# BATTERY-PCM.net
KiCad netlist of a schematic drawn in Altium Designer
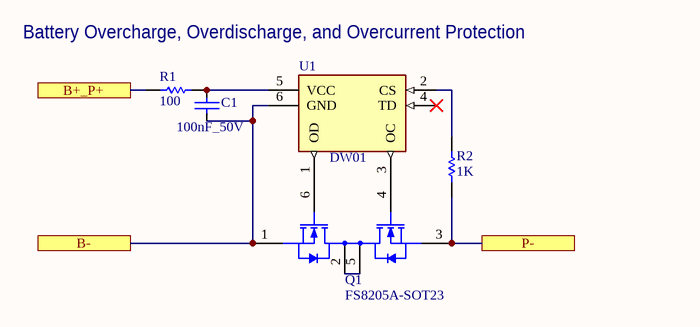
[diagram p0: BATTERY-PCM.SchDoc]

(export (version "E")
  (design (tool "Eeschema 10.0.6"))
  (components
    (comp (ref "C1")
      (value "100nF_50V")
      (footprint "C0402")
      (description "C0805 0.10 μF X7R 30ppm/°C 10.00% 50 V")
      (fields
        (field (name "MANUFACTURER") "KEMET")
        (field (name "MANUFACTURER PART NUMBER") "C0805C104K5RAC7411")
      )
      (libsource (lib "CustomLib-Package") (part "CAPACITOR"))
    )
    (comp (ref "Q1")
      (value "FS8205A-SOT23")
      (footprint "SOT-23-6")
      (description "Dual N-Channel Enhancement Mode Power MOSFET")
      (fields (field (name "MF") "Fortune Semiconductor") (field (name "MP") "FS8205A"))
      (libsource (lib "CustomLib-Package") (part "FS8205A-SOT23"))
    )
    (comp (ref "R1")
      (value "100")
      (footprint "R0402")
      (description "RES SMD 10K OHM 1% 1/8W 0805")
      (fields (field (name "TOLERANCE") "1%") (field (name "Comment") "CRG0805F10K"))
      (libsource (lib "CustomLib-Package") (part "RESISTOR"))
    )
    (comp (ref "R2")
      (value "1K")
      (footprint "R0402")
      (description "RES SMD 10K OHM 1% 1/8W 0805")
      (fields (field (name "TOLERANCE") "1%") (field (name "Comment") "CRG0805F10K"))
      (libsource (lib "CustomLib-Package") (part "RESISTOR"))
    )
    (comp (ref "U1")
      (value "DW01")
      (footprint "SOT-23-6")
      (description "One Cell Lithium-ion/Polymer Battery Protection IC")
      (fields (field (name "MF") "Fortune Semiconductor") (field (name "MP") "DW01A"))
      (libsource (lib "CustomLib-Package") (part "DW01"))
    )
  )
  (nets
    (net (code "1") (name "/B+_P+") (class "Default")
      (node (ref "R1") (pin "1") (pinfunction "1_1") (pintype "passive"))
    )
    (net (code "2") (name "/B-") (class "Default")
      (node (ref "C1") (pin "2") (pinfunction "2_2") (pintype "passive"))
      (node (ref "Q1") (pin "1") (pinfunction "S1_1") (pintype "passive"))
      (node (ref "U1") (pin "6") (pinfunction "GND_6") (pintype "power_in"))
    )
    (net (code "3") (name "/P-") (class "Default")
      (node (ref "Q1") (pin "3") (pinfunction "S2_3") (pintype "passive"))
      (node (ref "R2") (pin "2") (pinfunction "2_2") (pintype "passive"))
    )
    (net (code "4") (name "Net-(Q1-D1)") (class "Default")
      (node (ref "Q1") (pin "2") (pinfunction "D1_2") (pintype "passive"))
      (node (ref "Q1") (pin "5") (pinfunction "D2_5") (pintype "passive"))
    )
    (net (code "5") (name "Net-(Q1-G1)") (class "Default")
      (node (ref "Q1") (pin "6") (pinfunction "G1_6") (pintype "passive"))
      (node (ref "U1") (pin "1") (pinfunction "OD_1") (pintype "output"))
    )
    (net (code "6") (name "Net-(Q1-G2)") (class "Default")
      (node (ref "Q1") (pin "4") (pinfunction "G2_4") (pintype "passive"))
      (node (ref "U1") (pin "3") (pinfunction "OC_3") (pintype "output"))
    )
    (net (code "7") (name "Net-(U1-CS)") (class "Default")
      (node (ref "R2") (pin "1") (pinfunction "1_1") (pintype "passive"))
      (node (ref "U1") (pin "2") (pinfunction "CS_2") (pintype "input"))
    )
    (net (code "8") (name "Net-(U1-VCC)") (class "Default")
      (node (ref "C1") (pin "1") (pinfunction "1_1") (pintype "passive"))
      (node (ref "R1") (pin "2") (pinfunction "2_2") (pintype "passive"))
      (node (ref "U1") (pin "5") (pinfunction "VCC_5") (pintype "power_in"))
    )
    (net (code "9") (name "unconnected-(U1-TD-Pad4)") (class "Default")
      (node (ref "U1") (pin "4") (pinfunction "TD_4") (pintype "input+no_connect"))
    )
  )
)
